# PROC099B_Pwr_RST_LEDs.net
KiCad netlist of a schematic drawn in Altium Designer
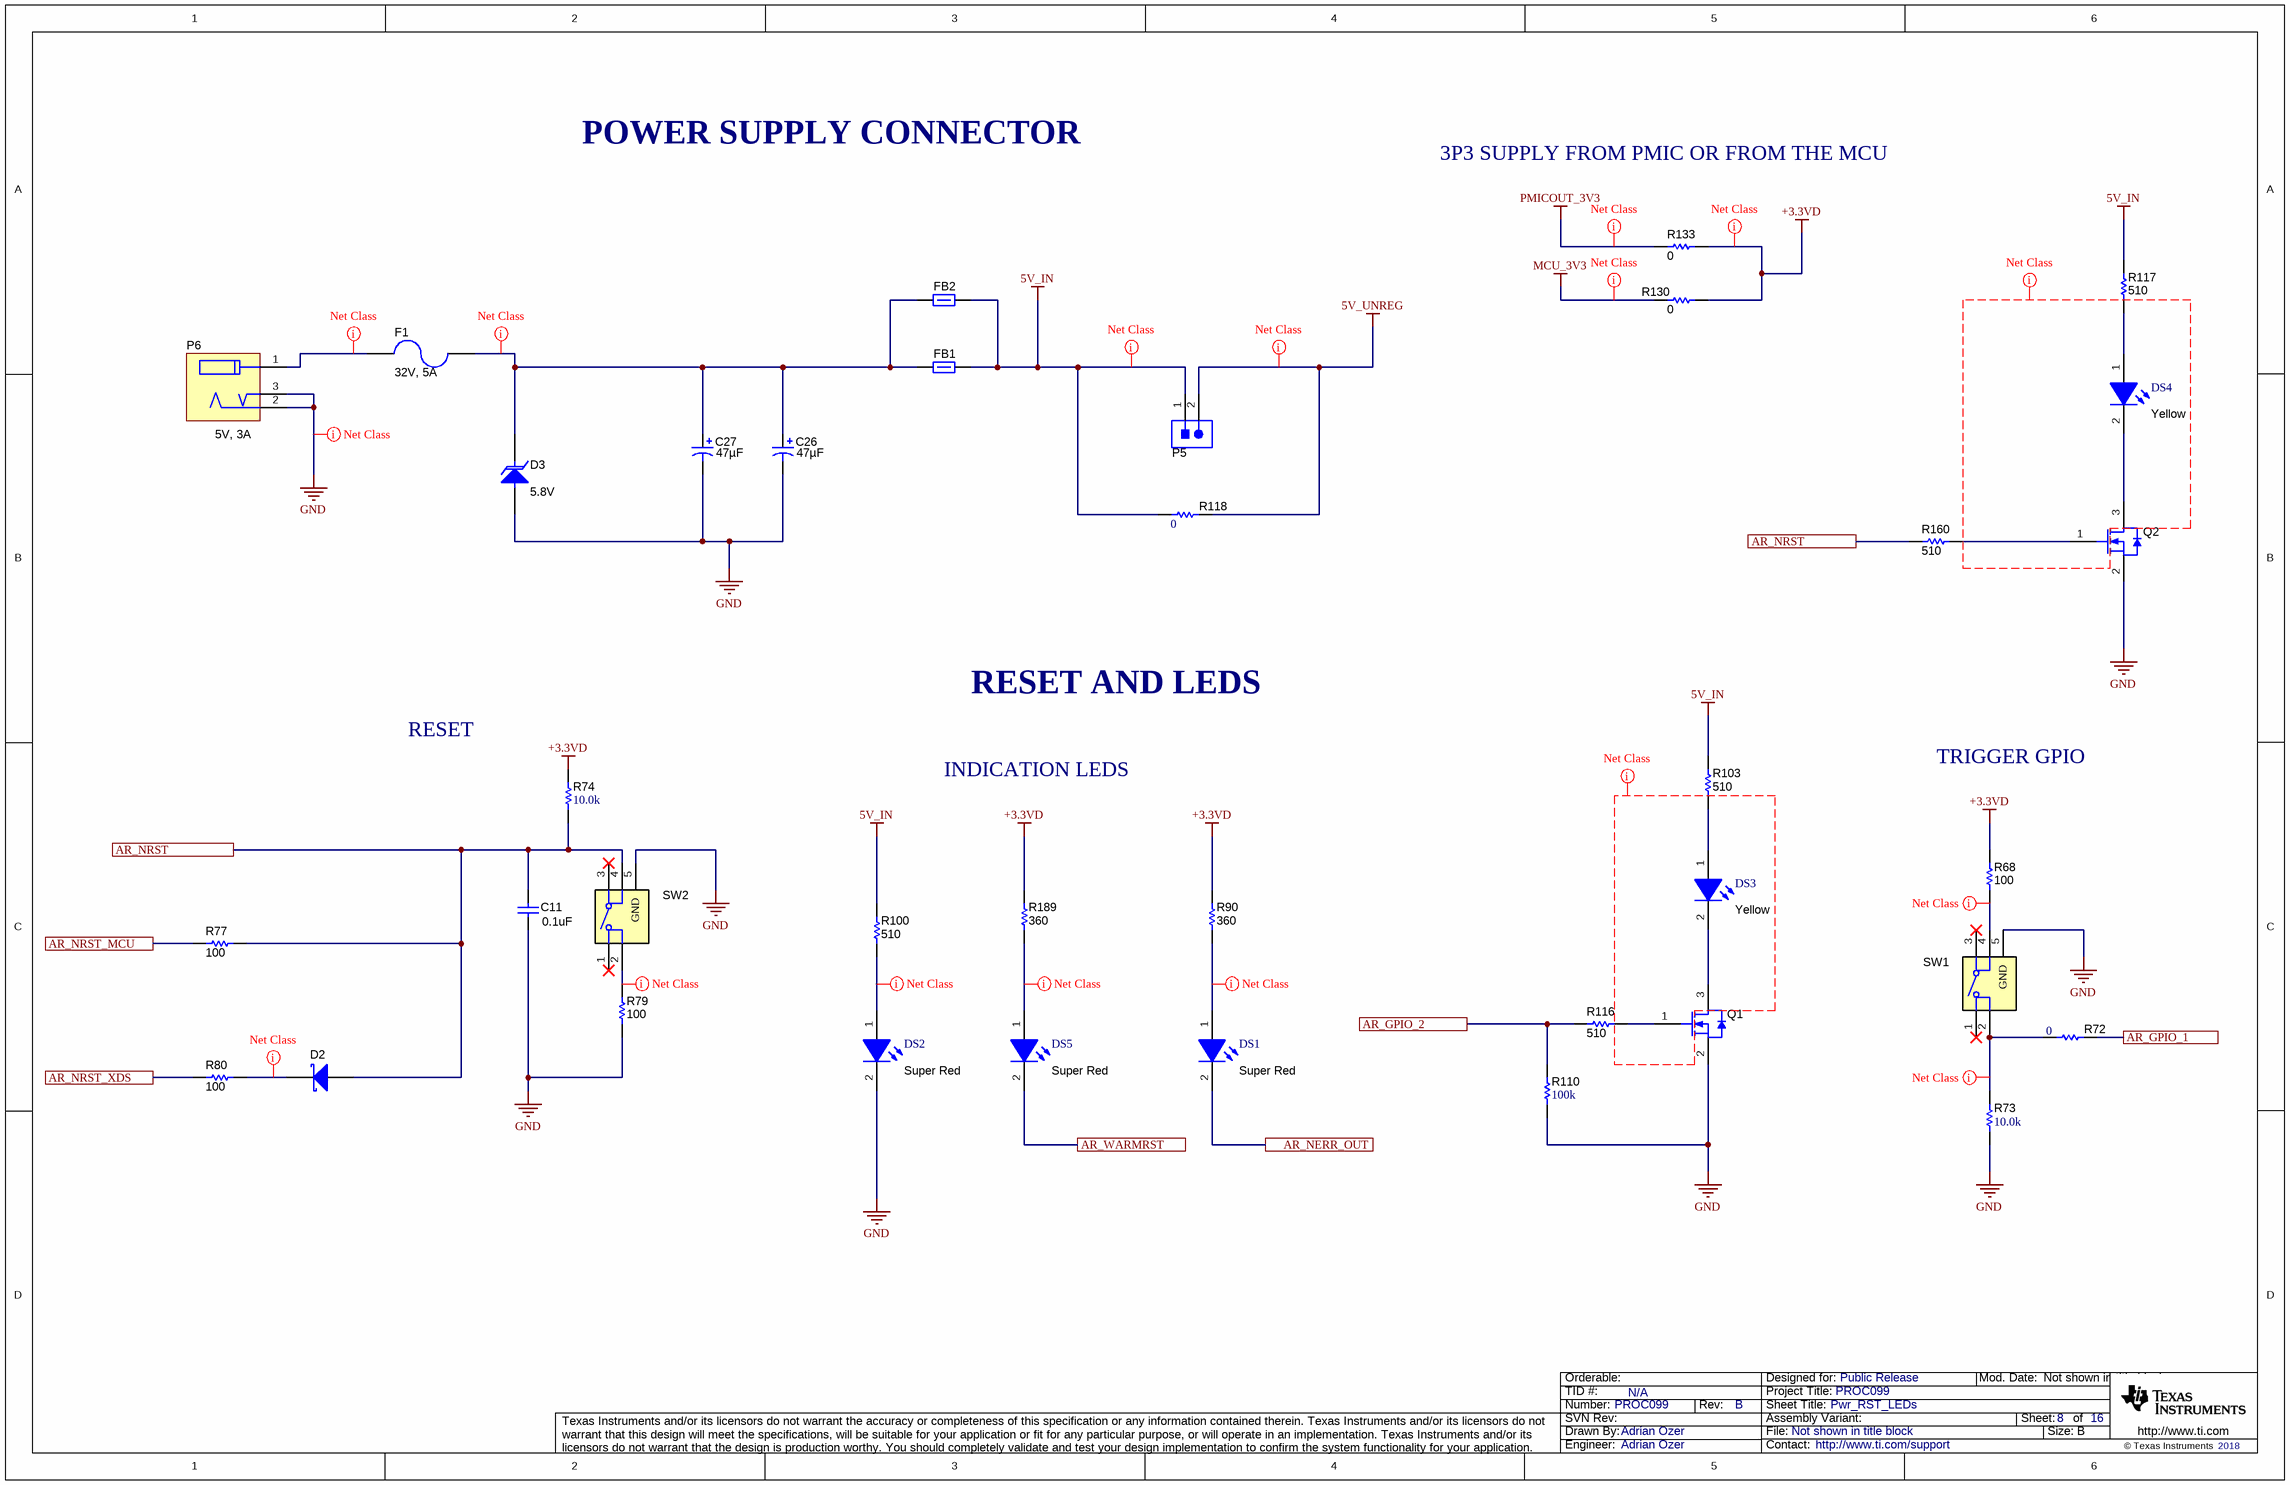
[diagram p0: PROC099B_Pwr_RST_LEDs.SchDoc]

(export (version "E")
  (design (tool "Eeschema 10.0.6"))
  (components
    (comp (ref "C11")
      (value "GCM155R71C104KA55D")
      (footprint "0402L")
      (description "CAP, CERM, 0.1 uF, 16 V, +/- 10%, X7R, 0402")
      (fields
        (field (name "MANUFACTURER") "MuRata")
        (field (name "VALUEDISPLAYED") "0.1uF")
        (field (name "PUBLISHER") "Texas Instruments")
      )
      (libsource (lib "Altium Vault - TI") (part "Capacitor"))
    )
    (comp (ref "C26")
      (value "T491B476K010AT")
      (footprint "3528-21")
      (description "CAP, TA, 47 µF, 10 V, +/- 10%, SMD")
      (fields (field (name "MANUFACTURER") "Kemet") (field (name "VALUEDISPLAYED") "47µF"))
      (libsource (lib "Altium Vault - TI") (part "Cap_Polarized"))
    )
    (comp (ref "C27")
      (value "T491B476K010AT")
      (footprint "3528-21")
      (description "CAP, TA, 47 µF, 10 V, +/- 10%, SMD")
      (fields (field (name "MANUFACTURER") "Kemet") (field (name "VALUEDISPLAYED") "47µF"))
      (libsource (lib "Altium Vault - TI") (part "Cap_Polarized"))
    )
    (comp (ref "D2")
      (value "SMS3923-040LF")
      (footprint "SOD-882")
      (description "Diode, Schottky,  V, 0.01 A, SOD-882")
      (fields (field (name "MANUFACTURER") "Skyworks Solutions"))
      (libsource (lib "Altium Vault - TI") (part "CMP-0078187-1"))
    )
    (comp (ref "D3")
      (value "5.8V")
      (footprint "SMB")
      (description "Diode, TVS, Uni, 5.8 V, 10.5 Vc, AEC-Q101, SMB")
      (fields (field (name "MANUFACTURER") "Littelfuse") (field (name "PARTNUMBER") "SZP6SMB6.8AT3G"))
      (libsource (lib "Altium Vault - TI") (part "Diode_TVS_Uni"))
    )
    (comp (ref "DS1")
      (value "Super Red")
      (footprint "SML-LX0603SRW_SuperRed")
      (description "LED, Super Red, SMD")
      (fields
        (field (name "MANUFACTURER") "Lumex")
        (field (name "PARTNUMBER") "SML-LX0603SRW-TR")
        (field (name "PUBLISHER") "Texas Instruments")
      )
      (libsource (lib "Altium Vault - TI") (part "CMP-0002876-1"))
    )
    (comp (ref "DS2")
      (value "Super Red")
      (footprint "SML-LX0603SRW_SuperRed")
      (description "LED, Super Red, SMD")
      (fields
        (field (name "MANUFACTURER") "Lumex")
        (field (name "PARTNUMBER") "SML-LX0603SRW-TR")
        (field (name "PUBLISHER") "Texas Instruments")
      )
      (libsource (lib "Altium Vault - TI") (part "CMP-0002876-1"))
    )
    (comp (ref "DS3")
      (value "Yellow")
      (footprint "SML-E1_Yellow")
      (description "LED, Yellow, SMD")
      (fields
        (field (name "MANUFACTURER") "Rohm")
        (field (name "PARTNUMBER") "SML-E12Y8WT86")
        (field (name "PUBLISHER") "Texas Instruments")
      )
      (libsource (lib "Altium Vault - TI") (part "LED"))
    )
    (comp (ref "DS4")
      (value "Yellow")
      (footprint "SML-E1_Yellow")
      (description "LED, Yellow, SMD")
      (fields
        (field (name "MANUFACTURER") "Rohm")
        (field (name "PARTNUMBER") "SML-E12Y8WT86")
        (field (name "PUBLISHER") "Texas Instruments")
      )
      (libsource (lib "Altium Vault - TI") (part "CMP-0002977-2"))
    )
    (comp (ref "DS5")
      (value "Super Red")
      (footprint "SML-LX0603SRW_SuperRed")
      (description "LED, Super Red, SMD")
      (fields
        (field (name "MANUFACTURER") "Lumex")
        (field (name "PARTNUMBER") "SML-LX0603SRW-TR")
        (field (name "PUBLISHER") "Texas Instruments")
      )
      (libsource (lib "Altium Vault - TI") (part "CMP-0002876-1"))
    )
    (comp (ref "F1")
      (value "32V, 5A")
      (footprint "1206")
      (description "Fuse, 5 A, 32VAC/VDC, SMD")
      (fields (field (name "MANUFACTURER") "Littelfuse") (field (name "PARTNUMBER") "0440005.WR"))
      (libsource (lib "Altium Vault - TI") (part "Fuse"))
    )
    (comp (ref "FB1")
      (value "BLM21PG300SH1D")
      (footprint "0805_HV")
      (description "Ferrite Bead, 30 ohm @ 100 MHz, 4 A, 0805")
      (fields (field (name "MANUFACTURER") "MuRata") (field (name "PUBLISHER") "Texas Instruments"))
      (libsource (lib "Altium Vault - TI") (part "CMP-0003364-1"))
    )
    (comp (ref "FB2")
      (value "BLM21PG300SH1D")
      (footprint "0805_HV")
      (description "Ferrite Bead, 30 ohm @ 100 MHz, 4 A, 0805")
      (fields (field (name "MANUFACTURER") "MuRata") (field (name "PUBLISHER") "Texas Instruments"))
      (libsource (lib "Altium Vault - TI") (part "CMP-0003364-1"))
    )
    (comp (ref "P5")
      (value "TSW-102-07-G-S")
      (footprint "TSW-102-07-G-S")
      (description "Header, 100mil, 2x1, Gold, TH")
      (fields (field (name "MANUFACTURER") "Samtec"))
      (libsource (lib "Altium Vault - TI") (part "Header_2x1"))
    )
    (comp (ref "P6")
      (value "PJ-002AH")
      (footprint "CUI_PJ-002AH")
      (description "DC POWER JACK, R/A, TH")
      (fields (field (name "MANUFACTURER") "CUI Inc."))
      (libsource (lib "Altium Vault - TI") (part "CONN_DC JACK"))
    )
    (comp (ref "Q1")
      (value "BSS123")
      (footprint "SOT-23")
      (description "MOSFET, N-CH, 100 V, 0.17 A, SOT-23")
      (fields
        (field (name "MANUFACTURER") "Fairchild Semiconductor")
        (field (name "PUBLISHER") "Texas Instruments")
      )
      (libsource (lib "Altium Vault - TI") (part "MOSFET_N_D3G1S2"))
    )
    (comp (ref "Q2")
      (value "BSS123")
      (footprint "SOT-23")
      (description "MOSFET, N-CH, 100 V, 0.17 A, SOT-23")
      (fields
        (field (name "MANUFACTURER") "Fairchild Semiconductor")
        (field (name "PUBLISHER") "Texas Instruments")
      )
      (libsource (lib "Altium Vault - TI") (part "MOSFET_N_D3G1S2"))
    )
    (comp (ref "R68")
      (value "ERJ-2GEJ101X")
      (footprint "0402L")
      (description "RES, 100, 5%, 0.1 W, AEC-Q200 Grade 0, 0402")
      (fields
        (field (name "MANUFACTURER") "Panasonic")
        (field (name "VALUEDISPLAYED") "100")
        (field (name "PUBLISHER") "Texas Instruments")
      )
      (libsource (lib "Altium Vault - TI") (part "Resistor"))
    )
    (comp (ref "R72")
      (value "CRCW02010000Z0ED")
      (footprint "0201_Silk")
      (description "RES, 0, 5%, 0.05 W, 0201")
      (fields (field (name "MANUFACTURER") "Vishay-Dale") (field (name "VALUEDISPLAYED") "0"))
      (libsource (lib "Altium Vault - TI") (part "Resistor"))
    )
    (comp (ref "R73")
      (value "CRCW040210K0FKED")
      (footprint "0402L")
      (description "RES, 10.0 k, 1%, 0.063 W, AEC-Q200 Grade 0, 0402")
      (fields (field (name "MANUFACTURER") "Vishay-Dale") (field (name "VALUEDISPLAYED") "10.0k"))
      (libsource (lib "Altium Vault - TI") (part "Resistor"))
    )
    (comp (ref "R74")
      (value "CRCW040210K0FKED")
      (footprint "0402L")
      (description "RES, 10.0 k, 1%, 0.063 W, AEC-Q200 Grade 0, 0402")
      (fields (field (name "MANUFACTURER") "Vishay-Dale") (field (name "VALUEDISPLAYED") "10.0k"))
      (libsource (lib "Altium Vault - TI") (part "Resistor"))
    )
    (comp (ref "R77")
      (value "ERJ-2GEJ101X")
      (footprint "0402L")
      (description "RES, 100, 5%, 0.1 W, AEC-Q200 Grade 0, 0402")
      (fields
        (field (name "MANUFACTURER") "Panasonic")
        (field (name "VALUEDISPLAYED") "100")
        (field (name "PUBLISHER") "Texas Instruments")
      )
      (libsource (lib "Altium Vault - TI") (part "Resistor"))
    )
    (comp (ref "R79")
      (value "ERJ-2GEJ101X")
      (footprint "0402L")
      (description "RES, 100, 5%, 0.1 W, AEC-Q200 Grade 0, 0402")
      (fields
        (field (name "MANUFACTURER") "Panasonic")
        (field (name "VALUEDISPLAYED") "100")
        (field (name "PUBLISHER") "Texas Instruments")
      )
      (libsource (lib "Altium Vault - TI") (part "Resistor"))
    )
    (comp (ref "R80")
      (value "ERJ-2GEJ101X")
      (footprint "0402L")
      (description "RES, 100, 5%, 0.1 W, AEC-Q200 Grade 0, 0402")
      (fields
        (field (name "MANUFACTURER") "Panasonic")
        (field (name "VALUEDISPLAYED") "100")
        (field (name "PUBLISHER") "Texas Instruments")
      )
      (libsource (lib "Altium Vault - TI") (part "Resistor"))
    )
    (comp (ref "R90")
      (value "ERJ-2GEJ361X")
      (footprint "0402L")
      (description "RES, 360, 5%, 0.1 W, AEC-Q200 Grade 0, 0402")
      (fields (field (name "MANUFACTURER") "Panasonic") (field (name "VALUEDISPLAYED") "360"))
      (libsource (lib "Altium Vault - TI") (part "Resistor"))
    )
    (comp (ref "R100")
      (value "ERJ-2GEJ511X")
      (footprint "0402L")
      (description "RES, 510, 5%, 0.1 W, AEC-Q200 Grade 0, 0402")
      (fields (field (name "MANUFACTURER") "Panasonic") (field (name "VALUEDISPLAYED") "510"))
      (libsource (lib "Altium Vault - TI") (part "Resistor"))
    )
    (comp (ref "R103")
      (value "ERJ-2GEJ511X")
      (footprint "0402L")
      (description "RES, 510, 5%, 0.1 W, AEC-Q200 Grade 0, 0402")
      (fields (field (name "MANUFACTURER") "Panasonic") (field (name "VALUEDISPLAYED") "510"))
      (libsource (lib "Altium Vault - TI") (part "Resistor"))
    )
    (comp (ref "R110")
      (value "CRCW0402100KFKED")
      (footprint "0402L")
      (description "RES, 100 k, 1%, 0.063 W, AEC-Q200 Grade 0, 0402")
      (fields (field (name "MANUFACTURER") "Vishay-Dale") (field (name "VALUEDISPLAYED") "100k"))
      (libsource (lib "Altium Vault - TI") (part "Resistor"))
    )
    (comp (ref "R116")
      (value "ERJ-2GEJ511X")
      (footprint "0402L")
      (description "RES, 510, 5%, 0.1 W, AEC-Q200 Grade 0, 0402")
      (fields (field (name "MANUFACTURER") "Panasonic") (field (name "VALUEDISPLAYED") "510"))
      (libsource (lib "Altium Vault - TI") (part "Resistor"))
    )
    (comp (ref "R117")
      (value "ERJ-2GEJ511X")
      (footprint "0402L")
      (description "RES, 510, 5%, 0.1 W, AEC-Q200 Grade 0, 0402")
      (fields (field (name "MANUFACTURER") "Panasonic") (field (name "VALUEDISPLAYED") "510"))
      (libsource (lib "Altium Vault - TI") (part "Resistor"))
    )
    (comp (ref "R118")
      (value "CRCW20100000Z0EF")
      (footprint "2010")
      (description "RES, 0, 5%, 0.75 W, AEC-Q200 Grade 0, 2010")
      (fields (field (name "MANUFACTURER") "Vishay-Dale") (field (name "VALUEDISPLAYED") "0"))
      (libsource (lib "Altium Vault - TI") (part "Resistor"))
    )
    (comp (ref "R130")
      (value "MCT06030Z0000ZP500")
      (footprint "0603")
      (description "RES, 0, 5%, 0.125 W, 0603")
      (fields
        (field (name "MANUFACTURER") "Vishay/Beyschlag")
        (field (name "VALUEDISPLAYED") "0")
        (field (name "PUBLISHER") "Texas Instruments")
      )
      (libsource (lib "Altium Vault - TI") (part "CMP-0025884-3"))
    )
    (comp (ref "R133")
      (value "MCT06030Z0000ZP500")
      (footprint "0603")
      (description "RES, 0, 5%, 0.125 W, 0603")
      (fields
        (field (name "MANUFACTURER") "Vishay/Beyschlag")
        (field (name "VALUEDISPLAYED") "0")
        (field (name "PUBLISHER") "Texas Instruments")
      )
      (libsource (lib "Altium Vault - TI") (part "Resistor"))
    )
    (comp (ref "R160")
      (value "ERJ-2GEJ511X")
      (footprint "0402L")
      (description "RES, 510, 5%, 0.1 W, AEC-Q200 Grade 0, 0402")
      (fields (field (name "MANUFACTURER") "Panasonic") (field (name "VALUEDISPLAYED") "510"))
      (libsource (lib "Altium Vault - TI") (part "Resistor"))
    )
    (comp (ref "R189")
      (value "ERJ-2GEJ361X")
      (footprint "0402L")
      (description "RES, 360, 5%, 0.1 W, AEC-Q200 Grade 0, 0402")
      (fields (field (name "MANUFACTURER") "Panasonic") (field (name "VALUEDISPLAYED") "360"))
      (libsource (lib "Altium Vault - TI") (part "Resistor"))
    )
    (comp (ref "SW1")
      (value "KMR243GLFG")
      (footprint "SW_KMR243GLFG")
      (description "Switch, SPST-NO, Off-Mom, 0.01 A, 32 VDC, SMD")
      (fields (field (name "MANUFACTURER") "C&K Components") (field (name "PUBLISHER") "Texas Instruments"))
      (libsource (lib "Altium Vault - TI") (part "CMP-0002325-1"))
    )
    (comp (ref "SW2")
      (value "KMR243GLFG")
      (footprint "SW_KMR243GLFG")
      (description "Switch, SPST-NO, Off-Mom, 0.01 A, 32 VDC, SMD")
      (fields (field (name "MANUFACTURER") "C&K Components") (field (name "PUBLISHER") "Texas Instruments"))
      (libsource (lib "Altium Vault - TI") (part "CMP-0002325-1"))
    )
  )
  (nets
    (net (code "1") (name "+3.3VD") (class "Default")
      (node (ref "R130") (pin "2") (pinfunction "2_2") (pintype "passive"))
      (node (ref "R133") (pin "2") (pinfunction "2_2") (pintype "passive"))
      (node (ref "R189") (pin "2") (pinfunction "2_2") (pintype "passive"))
      (node (ref "R68") (pin "2") (pinfunction "2_2") (pintype "passive"))
      (node (ref "R74") (pin "2") (pinfunction "2_2") (pintype "passive"))
      (node (ref "R90") (pin "2") (pinfunction "2_2") (pintype "passive"))
    )
    (net (code "2") (name "/AR_GPIO_1") (class "Default")
      (node (ref "R72") (pin "2") (pinfunction "2_2") (pintype "passive"))
    )
    (net (code "3") (name "/AR_GPIO_2") (class "Default")
      (node (ref "R110") (pin "2") (pinfunction "2_2") (pintype "passive"))
      (node (ref "R116") (pin "1") (pinfunction "1_1") (pintype "passive"))
    )
    (net (code "4") (name "/AR_NERR_OUT") (class "Default")
      (node (ref "DS1") (pin "2") (pinfunction "K_2") (pintype "passive"))
    )
    (net (code "5") (name "/AR_NRST") (class "Default")
      (node (ref "C11") (pin "2") (pinfunction "2_2") (pintype "passive"))
      (node (ref "D2") (pin "2") (pinfunction "A_2") (pintype "passive"))
      (node (ref "R160") (pin "1") (pinfunction "1_1") (pintype "passive"))
      (node (ref "R74") (pin "1") (pinfunction "1_1") (pintype "passive"))
      (node (ref "R77") (pin "2") (pinfunction "2_2") (pintype "passive"))
      (node (ref "SW2") (pin "4") (pinfunction "4_4") (pintype "passive"))
    )
    (net (code "6") (name "/AR_NRST_MCU") (class "Default")
      (node (ref "R77") (pin "1") (pinfunction "1_1") (pintype "passive"))
    )
    (net (code "7") (name "/AR_NRST_XDS") (class "Default")
      (node (ref "R80") (pin "1") (pinfunction "1_1") (pintype "passive"))
    )
    (net (code "8") (name "/AR_WARMRST") (class "Default")
      (node (ref "DS5") (pin "2") (pinfunction "K_2") (pintype "passive"))
    )
    (net (code "9") (name "5V_IN") (class "Default")
      (node (ref "FB1") (pin "2") (pinfunction "2_2") (pintype "passive"))
      (node (ref "FB2") (pin "2") (pinfunction "2_2") (pintype "passive"))
      (node (ref "P5") (pin "1") (pinfunction "1_1") (pintype "passive"))
      (node (ref "R100") (pin "2") (pinfunction "2_2") (pintype "passive"))
      (node (ref "R103") (pin "2") (pinfunction "2_2") (pintype "passive"))
      (node (ref "R117") (pin "2") (pinfunction "2_2") (pintype "passive"))
      (node (ref "R118") (pin "1") (pinfunction "1_1") (pintype "passive"))
    )
    (net (code "10") (name "5V_UNREG") (class "Default")
      (node (ref "P5") (pin "2") (pinfunction "2_2") (pintype "passive"))
      (node (ref "R118") (pin "2") (pinfunction "2_2") (pintype "passive"))
    )
    (net (code "11") (name "GND") (class "Default")
      (node (ref "C11") (pin "1") (pinfunction "1_1") (pintype "passive"))
      (node (ref "C26") (pin "2") (pinfunction "-_2") (pintype "passive"))
      (node (ref "C27") (pin "2") (pinfunction "-_2") (pintype "passive"))
      (node (ref "D3") (pin "2") (pinfunction "A_2") (pintype "passive"))
      (node (ref "DS2") (pin "2") (pinfunction "K_2") (pintype "passive"))
      (node (ref "P6") (pin "2") (pinfunction "2_2") (pintype "passive"))
      (node (ref "P6") (pin "3") (pinfunction "3_3") (pintype "passive"))
      (node (ref "Q1") (pin "2") (pinfunction "S_2") (pintype "passive"))
      (node (ref "Q2") (pin "2") (pinfunction "S_2") (pintype "passive"))
      (node (ref "R110") (pin "1") (pinfunction "1_1") (pintype "passive"))
      (node (ref "R73") (pin "1") (pinfunction "1_1") (pintype "passive"))
      (node (ref "R79") (pin "1") (pinfunction "1_1") (pintype "passive"))
      (node (ref "SW1") (pin "5") (pinfunction "GND_5") (pintype "passive"))
      (node (ref "SW2") (pin "5") (pinfunction "GND_5") (pintype "passive"))
    )
    (net (code "12") (name "MCU_3V3") (class "Default")
      (node (ref "R130") (pin "1") (pinfunction "1_1") (pintype "passive"))
    )
    (net (code "13") (name "Net-(C26-+)") (class "Default")
      (node (ref "C26") (pin "1") (pinfunction "+_1") (pintype "passive"))
      (node (ref "C27") (pin "1") (pinfunction "+_1") (pintype "passive"))
      (node (ref "D3") (pin "1") (pinfunction "K_1") (pintype "passive"))
      (node (ref "F1") (pin "1") (pinfunction "1_1") (pintype "passive"))
      (node (ref "FB1") (pin "1") (pinfunction "1_1") (pintype "passive"))
      (node (ref "FB2") (pin "1") (pinfunction "1_1") (pintype "passive"))
    )
    (net (code "14") (name "Net-(D2-K)") (class "Default")
      (node (ref "D2") (pin "1") (pinfunction "K_1") (pintype "passive"))
      (node (ref "R80") (pin "2") (pinfunction "2_2") (pintype "passive"))
    )
    (net (code "15") (name "Net-(DS1-A)") (class "Default")
      (node (ref "DS1") (pin "1") (pinfunction "A_1") (pintype "passive"))
      (node (ref "R90") (pin "1") (pinfunction "1_1") (pintype "passive"))
    )
    (net (code "16") (name "Net-(DS2-A)") (class "Default")
      (node (ref "DS2") (pin "1") (pinfunction "A_1") (pintype "passive"))
      (node (ref "R100") (pin "1") (pinfunction "1_1") (pintype "passive"))
    )
    (net (code "17") (name "Net-(DS3-A)") (class "Default")
      (node (ref "DS3") (pin "1") (pinfunction "A_1") (pintype "passive"))
      (node (ref "R103") (pin "1") (pinfunction "1_1") (pintype "passive"))
    )
    (net (code "18") (name "Net-(DS3-K)") (class "Default")
      (node (ref "DS3") (pin "2") (pinfunction "K_2") (pintype "passive"))
      (node (ref "Q1") (pin "3") (pinfunction "D_3") (pintype "passive"))
    )
    (net (code "19") (name "Net-(DS4-A)") (class "Default")
      (node (ref "DS4") (pin "1") (pinfunction "A_1") (pintype "passive"))
      (node (ref "R117") (pin "1") (pinfunction "1_1") (pintype "passive"))
    )
    (net (code "20") (name "Net-(DS4-K)") (class "Default")
      (node (ref "DS4") (pin "2") (pinfunction "K_2") (pintype "passive"))
      (node (ref "Q2") (pin "3") (pinfunction "D_3") (pintype "passive"))
    )
    (net (code "21") (name "Net-(DS5-A)") (class "Default")
      (node (ref "DS5") (pin "1") (pinfunction "A_1") (pintype "passive"))
      (node (ref "R189") (pin "1") (pinfunction "1_1") (pintype "passive"))
    )
    (net (code "22") (name "Net-(F1-Pad2)") (class "Default")
      (node (ref "F1") (pin "2") (pinfunction "2_2") (pintype "passive"))
      (node (ref "P6") (pin "1") (pinfunction "1_1") (pintype "passive"))
    )
    (net (code "23") (name "Net-(Q1-G)") (class "Default")
      (node (ref "Q1") (pin "1") (pinfunction "G_1") (pintype "passive"))
      (node (ref "R116") (pin "2") (pinfunction "2_2") (pintype "passive"))
    )
    (net (code "24") (name "Net-(Q2-G)") (class "Default")
      (node (ref "Q2") (pin "1") (pinfunction "G_1") (pintype "passive"))
      (node (ref "R160") (pin "2") (pinfunction "2_2") (pintype "passive"))
    )
    (net (code "25") (name "Net-(R68-Pad1)") (class "Default")
      (node (ref "R68") (pin "1") (pinfunction "1_1") (pintype "passive"))
      (node (ref "SW1") (pin "4") (pinfunction "4_4") (pintype "passive"))
    )
    (net (code "26") (name "Net-(R72-Pad1)") (class "Default")
      (node (ref "R72") (pin "1") (pinfunction "1_1") (pintype "passive"))
      (node (ref "R73") (pin "2") (pinfunction "2_2") (pintype "passive"))
      (node (ref "SW1") (pin "2") (pinfunction "2_2") (pintype "passive"))
    )
    (net (code "27") (name "Net-(R79-Pad2)") (class "Default")
      (node (ref "R79") (pin "2") (pinfunction "2_2") (pintype "passive"))
      (node (ref "SW2") (pin "2") (pinfunction "2_2") (pintype "passive"))
    )
    (net (code "28") (name "PMICOUT_3V3") (class "Default")
      (node (ref "R133") (pin "1") (pinfunction "1_1") (pintype "passive"))
    )
    (net (code "29") (name "unconnected-(SW1-Pad1)") (class "Default")
      (node (ref "SW1") (pin "1") (pinfunction "1_1") (pintype "passive+no_connect"))
    )
    (net (code "30") (name "unconnected-(SW1-Pad3)") (class "Default")
      (node (ref "SW1") (pin "3") (pinfunction "3_3") (pintype "passive+no_connect"))
    )
    (net (code "31") (name "unconnected-(SW2-Pad1)") (class "Default")
      (node (ref "SW2") (pin "1") (pinfunction "1_1") (pintype "passive+no_connect"))
    )
    (net (code "32") (name "unconnected-(SW2-Pad3)") (class "Default")
      (node (ref "SW2") (pin "3") (pinfunction "3_3") (pintype "passive+no_connect"))
    )
  )
)
